# FPGA_board_controller_sheet.net
KiCad netlist of a schematic drawn in Altium Designer
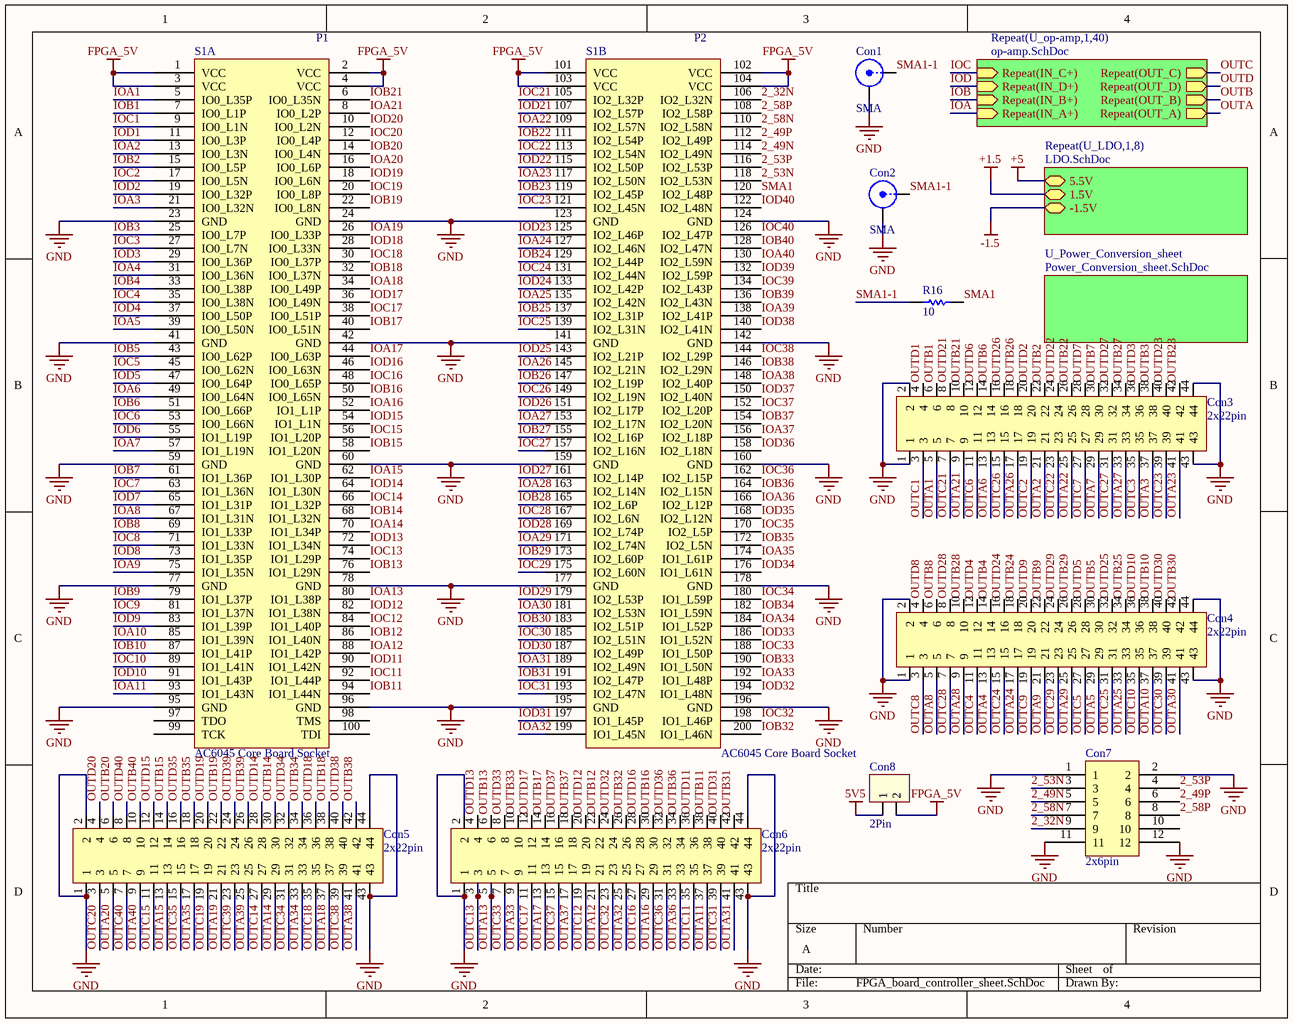
[diagram p0: FPGA_board_controller_sheet.SchDoc]

(export (version "E")
  (design (tool "Eeschema 10.0.6"))
  (components
    (comp (ref "Con1")
      (value "SMA")
      (footprint "SMA (3.5mm)")
      (libsource (lib "Schlib_FPGA_Controller") (part "SMA"))
    )
    (comp (ref "Con2")
      (value "SMA")
      (footprint "SMA (3.5mm)")
      (libsource (lib "Schlib_FPGA_Controller") (part "SMA"))
    )
    (comp (ref "Con3")
      (value "2x22pin")
      (footprint "2mm_2x22pin")
      (libsource (lib "Schlib_FPGA_Controller") (part "2x22pin"))
    )
    (comp (ref "Con4")
      (value "2x22pin")
      (footprint "2mm_2x22pin")
      (libsource (lib "Schlib_FPGA_Controller") (part "2x22pin"))
    )
    (comp (ref "Con5")
      (value "2x22pin")
      (footprint "2mm_2x22pin")
      (libsource (lib "Schlib_FPGA_Controller") (part "2x22pin"))
    )
    (comp (ref "Con6")
      (value "2x22pin")
      (footprint "2mm_2x22pin")
      (libsource (lib "Schlib_FPGA_Controller") (part "2x22pin"))
    )
    (comp (ref "Con7")
      (value "2x6pin")
      (footprint "2MM_2*6PIN")
      (libsource (lib "Schlib_FPGA_Controller") (part "2x6pin"))
    )
    (comp (ref "Con8")
      (value "2Pin")
      (footprint "XH2.54-2pin")
      (libsource (lib "Schlib_FPGA_Controller") (part "2Pin"))
    )
    (comp (ref "R16")
      (value "10")
      (footprint "R0603")
      (libsource (lib "Schlib_FPGA_Controller") (part "Resistor"))
    )
    (comp (ref "S1")
      (value "AC6045 Core Board Socket")
      (footprint "Core Board Socket")
      (libsource (lib "Schlib_FPGA_Controller") (part "AC6045 Core Board Socket"))
    )
  )
  (nets
    (net (code "4") (name "/2_32N") (class "Default")
      (node (ref "Con7") (pin "9") (pinfunction "9_9") (pintype "passive"))
      (node (ref "S1") (pin "106") (pinfunction "IO2_L32N_106") (pintype "passive"))
    )
    (net (code "5") (name "/2_49N") (class "Default")
      (node (ref "Con7") (pin "5") (pinfunction "5_5") (pintype "passive"))
      (node (ref "S1") (pin "114") (pinfunction "IO2_L49N_114") (pintype "passive"))
    )
    (net (code "6") (name "/2_49P") (class "Default")
      (node (ref "Con7") (pin "6") (pinfunction "6_6") (pintype "passive"))
      (node (ref "S1") (pin "112") (pinfunction "IO2_L49P_112") (pintype "passive"))
    )
    (net (code "7") (name "/2_53N") (class "Default")
      (node (ref "Con7") (pin "3") (pinfunction "3_3") (pintype "passive"))
      (node (ref "S1") (pin "118") (pinfunction "IO2_L53N_118") (pintype "passive"))
    )
    (net (code "8") (name "/2_53P") (class "Default")
      (node (ref "Con7") (pin "4") (pinfunction "4_4") (pintype "passive"))
      (node (ref "S1") (pin "116") (pinfunction "IO2_L53P_116") (pintype "passive"))
    )
    (net (code "9") (name "/2_58N") (class "Default")
      (node (ref "Con7") (pin "7") (pinfunction "7_7") (pintype "passive"))
      (node (ref "S1") (pin "110") (pinfunction "IO2_L58N_110") (pintype "passive"))
    )
    (net (code "10") (name "/2_58P") (class "Default")
      (node (ref "Con7") (pin "8") (pinfunction "8_8") (pintype "passive"))
      (node (ref "S1") (pin "108") (pinfunction "IO2_L58P_108") (pintype "passive"))
    )
    (net (code "12") (name "/IOA1") (class "Default")
      (node (ref "S1") (pin "5") (pinfunction "IO0_L35P_5") (pintype "passive"))
    )
    (net (code "13") (name "/IOA2") (class "Default")
      (node (ref "S1") (pin "13") (pinfunction "IO0_L3N_13") (pintype "passive"))
    )
    (net (code "14") (name "/IOA3") (class "Default")
      (node (ref "S1") (pin "21") (pinfunction "IO0_L32N_21") (pintype "passive"))
    )
    (net (code "15") (name "/IOA4") (class "Default")
      (node (ref "S1") (pin "31") (pinfunction "IO0_L36N_31") (pintype "passive"))
    )
    (net (code "16") (name "/IOA5") (class "Default")
      (node (ref "S1") (pin "39") (pinfunction "IO0_L50N_39") (pintype "passive"))
    )
    (net (code "17") (name "/IOA6") (class "Default")
      (node (ref "S1") (pin "49") (pinfunction "IO0_L64N_49") (pintype "passive"))
    )
    (net (code "18") (name "/IOA7") (class "Default")
      (node (ref "S1") (pin "57") (pinfunction "IO1_L19N_57") (pintype "passive"))
    )
    (net (code "19") (name "/IOA8") (class "Default")
      (node (ref "S1") (pin "67") (pinfunction "IO1_L31N_67") (pintype "passive"))
    )
    (net (code "20") (name "/IOA9") (class "Default")
      (node (ref "S1") (pin "75") (pinfunction "IO1_L35N_75") (pintype "passive"))
    )
    (net (code "21") (name "/IOA10") (class "Default")
      (node (ref "S1") (pin "85") (pinfunction "IO1_L39N_85") (pintype "passive"))
    )
    (net (code "22") (name "/IOA11") (class "Default")
      (node (ref "S1") (pin "93") (pinfunction "IO1_L43N_93") (pintype "passive"))
    )
    (net (code "23") (name "/IOA12") (class "Default")
      (node (ref "S1") (pin "88") (pinfunction "IO1_L42P_88") (pintype "passive"))
    )
    (net (code "24") (name "/IOA13") (class "Default")
      (node (ref "S1") (pin "80") (pinfunction "IO1_L38P_80") (pintype "passive"))
    )
    (net (code "25") (name "/IOA14") (class "Default")
      (node (ref "S1") (pin "70") (pinfunction "IO1_L34P_70") (pintype "passive"))
    )
    (net (code "26") (name "/IOA15") (class "Default")
      (node (ref "S1") (pin "62") (pinfunction "IO1_L30P_62") (pintype "passive"))
    )
    (net (code "27") (name "/IOA16") (class "Default")
      (node (ref "S1") (pin "52") (pinfunction "IO1_L1P_52") (pintype "passive"))
    )
    (net (code "28") (name "/IOA17") (class "Default")
      (node (ref "S1") (pin "44") (pinfunction "IO0_L63P_44") (pintype "passive"))
    )
    (net (code "29") (name "/IOA18") (class "Default")
      (node (ref "S1") (pin "34") (pinfunction "IO0_L49P_34") (pintype "passive"))
    )
    (net (code "30") (name "/IOA19") (class "Default")
      (node (ref "S1") (pin "26") (pinfunction "IO0_L33P_26") (pintype "passive"))
    )
    (net (code "31") (name "/IOA20") (class "Default")
      (node (ref "S1") (pin "16") (pinfunction "IO0_L6P_16") (pintype "passive"))
    )
    (net (code "32") (name "/IOA21") (class "Default")
      (node (ref "S1") (pin "8") (pinfunction "IO0_L2P_8") (pintype "passive"))
    )
    (net (code "33") (name "/IOA22") (class "Default")
      (node (ref "S1") (pin "109") (pinfunction "IO2_L57N_109") (pintype "passive"))
    )
    (net (code "34") (name "/IOA23") (class "Default")
      (node (ref "S1") (pin "117") (pinfunction "IO2_L50N_117") (pintype "passive"))
    )
    (net (code "35") (name "/IOA24") (class "Default")
      (node (ref "S1") (pin "127") (pinfunction "IO2_L46N_127") (pintype "passive"))
    )
    (net (code "36") (name "/IOA25") (class "Default")
      (node (ref "S1") (pin "135") (pinfunction "IO2_L42N_135") (pintype "passive"))
    )
    (net (code "37") (name "/IOA26") (class "Default")
      (node (ref "S1") (pin "145") (pinfunction "IO2_L21N_145") (pintype "passive"))
    )
    (net (code "38") (name "/IOA27") (class "Default")
      (node (ref "S1") (pin "153") (pinfunction "IO2_L17N_153") (pintype "passive"))
    )
    (net (code "39") (name "/IOA28") (class "Default")
      (node (ref "S1") (pin "163") (pinfunction "IO2_L14N_163") (pintype "passive"))
    )
    (net (code "40") (name "/IOA29") (class "Default")
      (node (ref "S1") (pin "171") (pinfunction "IO2_L74N_171") (pintype "passive"))
    )
    (net (code "41") (name "/IOA30") (class "Default")
      (node (ref "S1") (pin "181") (pinfunction "IO2_L53N_181") (pintype "passive"))
    )
    (net (code "42") (name "/IOA31") (class "Default")
      (node (ref "S1") (pin "189") (pinfunction "IO2_L49N_189") (pintype "passive"))
    )
    (net (code "43") (name "/IOA32") (class "Default")
      (node (ref "S1") (pin "199") (pinfunction "IO1_L45N_199") (pintype "passive"))
    )
    (net (code "44") (name "/IOA33") (class "Default")
      (node (ref "S1") (pin "192") (pinfunction "IO1_L48P_192") (pintype "passive"))
    )
    (net (code "45") (name "/IOA34") (class "Default")
      (node (ref "S1") (pin "184") (pinfunction "IO1_L52P_184") (pintype "passive"))
    )
    (net (code "46") (name "/IOA35") (class "Default")
      (node (ref "S1") (pin "174") (pinfunction "IO1_L61P_174") (pintype "passive"))
    )
    (net (code "47") (name "/IOA36") (class "Default")
      (node (ref "S1") (pin "166") (pinfunction "IO2_L12P_166") (pintype "passive"))
    )
    (net (code "48") (name "/IOA37") (class "Default")
      (node (ref "S1") (pin "156") (pinfunction "IO2_L18P_156") (pintype "passive"))
    )
    (net (code "49") (name "/IOA38") (class "Default")
      (node (ref "S1") (pin "148") (pinfunction "IO2_L40P_148") (pintype "passive"))
    )
    (net (code "50") (name "/IOA39") (class "Default")
      (node (ref "S1") (pin "138") (pinfunction "IO2_L41P_138") (pintype "passive"))
    )
    (net (code "51") (name "/IOA40") (class "Default")
      (node (ref "S1") (pin "130") (pinfunction "IO2_L59N_130") (pintype "passive"))
    )
    (net (code "53") (name "/IOB1") (class "Default")
      (node (ref "S1") (pin "7") (pinfunction "IO0_L1P_7") (pintype "passive"))
    )
    (net (code "54") (name "/IOB2") (class "Default")
      (node (ref "S1") (pin "15") (pinfunction "IO0_L5P_15") (pintype "passive"))
    )
    (net (code "55") (name "/IOB3") (class "Default")
      (node (ref "S1") (pin "25") (pinfunction "IO0_L7P_25") (pintype "passive"))
    )
    (net (code "56") (name "/IOB4") (class "Default")
      (node (ref "S1") (pin "33") (pinfunction "IO0_L38P_33") (pintype "passive"))
    )
    (net (code "57") (name "/IOB5") (class "Default")
      (node (ref "S1") (pin "43") (pinfunction "IO0_L62P_43") (pintype "passive"))
    )
    (net (code "58") (name "/IOB6") (class "Default")
      (node (ref "S1") (pin "51") (pinfunction "IO0_L66P_51") (pintype "passive"))
    )
    (net (code "59") (name "/IOB7") (class "Default")
      (node (ref "S1") (pin "61") (pinfunction "IO1_L36P_61") (pintype "passive"))
    )
    (net (code "60") (name "/IOB8") (class "Default")
      (node (ref "S1") (pin "69") (pinfunction "IO1_L33P_69") (pintype "passive"))
    )
    (net (code "61") (name "/IOB9") (class "Default")
      (node (ref "S1") (pin "79") (pinfunction "IO1_L37P_79") (pintype "passive"))
    )
    (net (code "62") (name "/IOB10") (class "Default")
      (node (ref "S1") (pin "87") (pinfunction "IO1_L41P_87") (pintype "passive"))
    )
    (net (code "63") (name "/IOB11") (class "Default")
      (node (ref "S1") (pin "94") (pinfunction "IO1_L44N_94") (pintype "passive"))
    )
    (net (code "64") (name "/IOB12") (class "Default")
      (node (ref "S1") (pin "86") (pinfunction "IO1_L40N_86") (pintype "passive"))
    )
    (net (code "65") (name "/IOB13") (class "Default")
      (node (ref "S1") (pin "76") (pinfunction "IO1_L29N_76") (pintype "passive"))
    )
    (net (code "66") (name "/IOB14") (class "Default")
      (node (ref "S1") (pin "68") (pinfunction "IO1_L32N_68") (pintype "passive"))
    )
    (net (code "67") (name "/IOB15") (class "Default")
      (node (ref "S1") (pin "58") (pinfunction "IO1_L20N_58") (pintype "passive"))
    )
    (net (code "68") (name "/IOB16") (class "Default")
      (node (ref "S1") (pin "50") (pinfunction "IO0_L65N_50") (pintype "passive"))
    )
    (net (code "69") (name "/IOB17") (class "Default")
      (node (ref "S1") (pin "40") (pinfunction "IO0_L51N_40") (pintype "passive"))
    )
    (net (code "70") (name "/IOB18") (class "Default")
      (node (ref "S1") (pin "32") (pinfunction "IO0_L37N_32") (pintype "passive"))
    )
    (net (code "71") (name "/IOB19") (class "Default")
      (node (ref "S1") (pin "22") (pinfunction "IO0_L8N_22") (pintype "passive"))
    )
    (net (code "72") (name "/IOB20") (class "Default")
      (node (ref "S1") (pin "14") (pinfunction "IO0_L4N_14") (pintype "passive"))
    )
    (net (code "73") (name "/IOB21") (class "Default")
      (node (ref "S1") (pin "6") (pinfunction "IO0_L35N_6") (pintype "passive"))
    )
    (net (code "74") (name "/IOB22") (class "Default")
      (node (ref "S1") (pin "111") (pinfunction "IO2_L54P_111") (pintype "passive"))
    )
    (net (code "75") (name "/IOB23") (class "Default")
      (node (ref "S1") (pin "119") (pinfunction "IO2_L45P_119") (pintype "passive"))
    )
    (net (code "76") (name "/IOB24") (class "Default")
      (node (ref "S1") (pin "129") (pinfunction "IO2_L44P_129") (pintype "passive"))
    )
    (net (code "77") (name "/IOB25") (class "Default")
      (node (ref "S1") (pin "137") (pinfunction "IO2_L31P_137") (pintype "passive"))
    )
    (net (code "78") (name "/IOB26") (class "Default")
      (node (ref "S1") (pin "147") (pinfunction "IO2_L19P_147") (pintype "passive"))
    )
    (net (code "79") (name "/IOB27") (class "Default")
      (node (ref "S1") (pin "155") (pinfunction "IO2_L16P_155") (pintype "passive"))
    )
    (net (code "80") (name "/IOB28") (class "Default")
      (node (ref "S1") (pin "165") (pinfunction "IO2_L6P_165") (pintype "passive"))
    )
    (net (code "81") (name "/IOB29") (class "Default")
      (node (ref "S1") (pin "173") (pinfunction "IO2_L60P_173") (pintype "passive"))
    )
    (net (code "82") (name "/IOB30") (class "Default")
      (node (ref "S1") (pin "183") (pinfunction "IO2_L51P_183") (pintype "passive"))
    )
    (net (code "83") (name "/IOB31") (class "Default")
      (node (ref "S1") (pin "191") (pinfunction "IO2_L47P_191") (pintype "passive"))
    )
    (net (code "84") (name "/IOB32") (class "Default")
      (node (ref "S1") (pin "200") (pinfunction "IO1_L46N_200") (pintype "passive"))
    )
    (net (code "85") (name "/IOB33") (class "Default")
      (node (ref "S1") (pin "190") (pinfunction "IO1_L50N_190") (pintype "passive"))
    )
    (net (code "86") (name "/IOB34") (class "Default")
      (node (ref "S1") (pin "182") (pinfunction "IO1_L59N_182") (pintype "passive"))
    )
    (net (code "87") (name "/IOB35") (class "Default")
      (node (ref "S1") (pin "172") (pinfunction "IO2_L5N_172") (pintype "passive"))
    )
    (net (code "88") (name "/IOB36") (class "Default")
      (node (ref "S1") (pin "164") (pinfunction "IO2_L15N_164") (pintype "passive"))
    )
    (net (code "89") (name "/IOB37") (class "Default")
      (node (ref "S1") (pin "154") (pinfunction "IO2_L20N_154") (pintype "passive"))
    )
    (net (code "90") (name "/IOB38") (class "Default")
      (node (ref "S1") (pin "146") (pinfunction "IO2_L29N_146") (pintype "passive"))
    )
    (net (code "91") (name "/IOB39") (class "Default")
      (node (ref "S1") (pin "136") (pinfunction "IO2_L43N_136") (pintype "passive"))
    )
    (net (code "92") (name "/IOB40") (class "Default")
      (node (ref "S1") (pin "128") (pinfunction "IO2_L47N_128") (pintype "passive"))
    )
    (net (code "94") (name "/IOC1") (class "Default")
      (node (ref "S1") (pin "9") (pinfunction "IO0_L1N_9") (pintype "passive"))
    )
    (net (code "95") (name "/IOC2") (class "Default")
      (node (ref "S1") (pin "17") (pinfunction "IO0_L5N_17") (pintype "passive"))
    )
    (net (code "96") (name "/IOC3") (class "Default")
      (node (ref "S1") (pin "27") (pinfunction "IO0_L7N_27") (pintype "passive"))
    )
    (net (code "97") (name "/IOC4") (class "Default")
      (node (ref "S1") (pin "35") (pinfunction "IO0_L38N_35") (pintype "passive"))
    )
    (net (code "98") (name "/IOC5") (class "Default")
      (node (ref "S1") (pin "45") (pinfunction "IO0_L62N_45") (pintype "passive"))
    )
    (net (code "99") (name "/IOC6") (class "Default")
      (node (ref "S1") (pin "53") (pinfunction "IO0_L66N_53") (pintype "passive"))
    )
    (net (code "100") (name "/IOC7") (class "Default")
      (node (ref "S1") (pin "63") (pinfunction "IO1_L36N_63") (pintype "passive"))
    )
    (net (code "101") (name "/IOC8") (class "Default")
      (node (ref "S1") (pin "71") (pinfunction "IO1_L33N_71") (pintype "passive"))
    )
    (net (code "102") (name "/IOC9") (class "Default")
      (node (ref "S1") (pin "81") (pinfunction "IO1_L37N_81") (pintype "passive"))
    )
    (net (code "103") (name "/IOC10") (class "Default")
      (node (ref "S1") (pin "89") (pinfunction "IO1_L41N_89") (pintype "passive"))
    )
    (net (code "104") (name "/IOC11") (class "Default")
      (node (ref "S1") (pin "92") (pinfunction "IO1_L44P_92") (pintype "passive"))
    )
    (net (code "105") (name "/IOC12") (class "Default")
      (node (ref "S1") (pin "84") (pinfunction "IO1_L40P_84") (pintype "passive"))
    )
    (net (code "106") (name "/IOC13") (class "Default")
      (node (ref "S1") (pin "74") (pinfunction "IO1_L29P_74") (pintype "passive"))
    )
    (net (code "107") (name "/IOC14") (class "Default")
      (node (ref "S1") (pin "66") (pinfunction "IO1_L32P_66") (pintype "passive"))
    )
    (net (code "108") (name "/IOC15") (class "Default")
      (node (ref "S1") (pin "56") (pinfunction "IO1_L20P_56") (pintype "passive"))
    )
    (net (code "109") (name "/IOC16") (class "Default")
      (node (ref "S1") (pin "48") (pinfunction "IO0_L65P_48") (pintype "passive"))
    )
    (net (code "110") (name "/IOC17") (class "Default")
      (node (ref "S1") (pin "38") (pinfunction "IO0_L51P_38") (pintype "passive"))
    )
    (net (code "111") (name "/IOC18") (class "Default")
      (node (ref "S1") (pin "30") (pinfunction "IO0_L37P_30") (pintype "passive"))
    )
    (net (code "112") (name "/IOC19") (class "Default")
      (node (ref "S1") (pin "20") (pinfunction "IO0_L8P_20") (pintype "passive"))
    )
    (net (code "113") (name "/IOC20") (class "Default")
      (node (ref "S1") (pin "12") (pinfunction "IO0_L4P_12") (pintype "passive"))
    )
    (net (code "114") (name "/IOC21") (class "Default")
      (node (ref "S1") (pin "105") (pinfunction "IO2_L32P_105") (pintype "passive"))
    )
    (net (code "115") (name "/IOC22") (class "Default")
      (node (ref "S1") (pin "113") (pinfunction "IO2_L54N_113") (pintype "passive"))
    )
    (net (code "116") (name "/IOC23") (class "Default")
      (node (ref "S1") (pin "121") (pinfunction "IO2_L45N_121") (pintype "passive"))
    )
    (net (code "117") (name "/IOC24") (class "Default")
      (node (ref "S1") (pin "131") (pinfunction "IO2_L44N_131") (pintype "passive"))
    )
    (net (code "118") (name "/IOC25") (class "Default")
      (node (ref "S1") (pin "139") (pinfunction "IO2_L31N_139") (pintype "passive"))
    )
    (net (code "119") (name "/IOC26") (class "Default")
      (node (ref "S1") (pin "149") (pinfunction "IO2_L19N_149") (pintype "passive"))
    )
    (net (code "120") (name "/IOC27") (class "Default")
      (node (ref "S1") (pin "157") (pinfunction "IO2_L16N_157") (pintype "passive"))
    )
    (net (code "121") (name "/IOC28") (class "Default")
      (node (ref "S1") (pin "167") (pinfunction "IO2_L6N_167") (pintype "passive"))
    )
    (net (code "122") (name "/IOC29") (class "Default")
      (node (ref "S1") (pin "175") (pinfunction "IO2_L60N_175") (pintype "passive"))
    )
    (net (code "123") (name "/IOC30") (class "Default")
      (node (ref "S1") (pin "185") (pinfunction "IO2_L51N_185") (pintype "passive"))
    )
    (net (code "124") (name "/IOC31") (class "Default")
      (node (ref "S1") (pin "193") (pinfunction "IO2_L47N_193") (pintype "passive"))
    )
    (net (code "125") (name "/IOC32") (class "Default")
      (node (ref "S1") (pin "198") (pinfunction "IO1_L46P_198") (pintype "passive"))
    )
    (net (code "126") (name "/IOC33") (class "Default")
      (node (ref "S1") (pin "188") (pinfunction "IO1_L50P_188") (pintype "passive"))
    )
    (net (code "127") (name "/IOC34") (class "Default")
      (node (ref "S1") (pin "180") (pinfunction "IO1_L59P_180") (pintype "passive"))
    )
    (net (code "128") (name "/IOC35") (class "Default")
      (node (ref "S1") (pin "170") (pinfunction "IO2_L5P_170") (pintype "passive"))
    )
    (net (code "129") (name "/IOC36") (class "Default")
      (node (ref "S1") (pin "162") (pinfunction "IO2_L15P_162") (pintype "passive"))
    )
    (net (code "130") (name "/IOC37") (class "Default")
      (node (ref "S1") (pin "152") (pinfunction "IO2_L20P_152") (pintype "passive"))
    )
    (net (code "131") (name "/IOC38") (class "Default")
      (node (ref "S1") (pin "144") (pinfunction "IOS_L29P_144") (pintype "passive"))
    )
    (net (code "132") (name "/IOC39") (class "Default")
      (node (ref "S1") (pin "134") (pinfunction "IO2_L43P_134") (pintype "passive"))
    )
    (net (code "133") (name "/IOC40") (class "Default")
      (node (ref "S1") (pin "126") (pinfunction "IO2_L47P_126") (pintype "passive"))
    )
    (net (code "135") (name "/IOD1") (class "Default")
      (node (ref "S1") (pin "11") (pinfunction "IO0_L3P_11") (pintype "passive"))
    )
    (net (code "136") (name "/IOD2") (class "Default")
      (node (ref "S1") (pin "19") (pinfunction "IO0_L32P_19") (pintype "passive"))
    )
    (net (code "137") (name "/IOD3") (class "Default")
      (node (ref "S1") (pin "29") (pinfunction "IO0_L36P_29") (pintype "passive"))
    )
    (net (code "138") (name "/IOD4") (class "Default")
      (node (ref "S1") (pin "37") (pinfunction "IO0_L50P_37") (pintype "passive"))
    )
    (net (code "139") (name "/IOD5") (class "Default")
      (node (ref "S1") (pin "47") (pinfunction "IO0_L64P_47") (pintype "passive"))
    )
    (net (code "140") (name "/IOD6") (class "Default")
      (node (ref "S1") (pin "55") (pinfunction "IO1_L19P_55") (pintype "passive"))
    )
    (net (code "141") (name "/IOD7") (class "Default")
      (node (ref "S1") (pin "65") (pinfunction "IO1_L31P_65") (pintype "passive"))
    )
    (net (code "142") (name "/IOD8") (class "Default")
      (node (ref "S1") (pin "73") (pinfunction "IO1_L35P_73") (pintype "passive"))
    )
    (net (code "143") (name "/IOD9") (class "Default")
      (node (ref "S1") (pin "83") (pinfunction "IO1_L39P_83") (pintype "passive"))
    )
    (net (code "144") (name "/IOD10") (class "Default")
      (node (ref "S1") (pin "91") (pinfunction "IO1_L43P_91") (pintype "passive"))
    )
    (net (code "145") (name "/IOD11") (class "Default")
      (node (ref "S1") (pin "90") (pinfunction "IO1_L42N_90") (pintype "passive"))
    )
    (net (code "146") (name "/IOD12") (class "Default")
      (node (ref "S1") (pin "82") (pinfunction "IO1_L38N_82") (pintype "passive"))
    )
    (net (code "147") (name "/IOD13") (class "Default")
      (node (ref "S1") (pin "72") (pinfunction "IO1_L34N_72") (pintype "passive"))
    )
    (net (code "148") (name "/IOD14") (class "Default")
      (node (ref "S1") (pin "64") (pinfunction "IO1_L30N_64") (pintype "passive"))
    )
    (net (code "149") (name "/IOD15") (class "Default")
      (node (ref "S1") (pin "54") (pinfunction "IO1_L1N_54") (pintype "passive"))
    )
    (net (code "150") (name "/IOD16") (class "Default")
      (node (ref "S1") (pin "46") (pinfunction "IO0_L63N_46") (pintype "passive"))
    )
    (net (code "151") (name "/IOD17") (class "Default")
      (node (ref "S1") (pin "36") (pinfunction "IO0_L49N_36") (pintype "passive"))
    )
    (net (code "152") (name "/IOD18") (class "Default")
      (node (ref "S1") (pin "28") (pinfunction "IO0_L33N_28") (pintype "passive"))
    )
    (net (code "153") (name "/IOD19") (class "Default")
      (node (ref "S1") (pin "18") (pinfunction "IO0_L6N_18") (pintype "passive"))
    )
    (net (code "154") (name "/IOD20") (class "Default")
      (node (ref "S1") (pin "10") (pinfunction "IO0_L2N_10") (pintype "passive"))
    )
    (net (code "155") (name "/IOD21") (class "Default")
      (node (ref "S1") (pin "107") (pinfunction "IO2_L57P_107") (pintype "passive"))
    )
    (net (code "156") (name "/IOD22") (class "Default")
      (node (ref "S1") (pin "115") (pinfunction "IO2_L50P_115") (pintype "passive"))
    )
    (net (code "157") (name "/IOD23") (class "Default")
      (node (ref "S1") (pin "125") (pinfunction "IO2_L46P_125") (pintype "passive"))
    )
    (net (code "158") (name "/IOD24") (class "Default")
      (node (ref "S1") (pin "133") (pinfunction "IO2_L42P_133") (pintype "passive"))
    )
    (net (code "159") (name "/IOD25") (class "Default")
      (node (ref "S1") (pin "143") (pinfunction "IO2_L21P_143") (pintype "passive"))
    )
    (net (code "160") (name "/IOD26") (class "Default")
      (node (ref "S1") (pin "151") (pinfunction "IO2_L17P_151") (pintype "passive"))
    )
    (net (code "161") (name "/IOD27") (class "Default")
      (node (ref "S1") (pin "161") (pinfunction "IO2_L14P_161") (pintype "passive"))
    )
    (net (code "162") (name "/IOD28") (class "Default")
      (node (ref "S1") (pin "169") (pinfunction "IO2_L74P_169") (pintype "passive"))
    )
    (net (code "163") (name "/IOD29") (class "Default")
      (node (ref "S1") (pin "179") (pinfunction "IO2_L53P_179") (pintype "passive"))
    )
    (net (code "164") (name "/IOD30") (class "Default")
      (node (ref "S1") (pin "187") (pinfunction "IO2_L49P_187") (pintype "passive"))
    )
    (net (code "165") (name "/IOD31") (class "Default")
      (node (ref "S1") (pin "197") (pinfunction "IO1_L45P_197") (pintype "passive"))
    )
    (net (code "166") (name "/IOD32") (class "Default")
      (node (ref "S1") (pin "194") (pinfunction "IO1_L48N_194") (pintype "passive"))
    )
    (net (code "167") (name "/IOD33") (class "Default")
      (node (ref "S1") (pin "186") (pinfunction "IO1_L52N_186") (pintype "passive"))
    )
    (net (code "168") (name "/IOD34") (class "Default")
      (node (ref "S1") (pin "176") (pinfunction "IO1_L61N_176") (pintype "passive"))
    )
    (net (code "169") (name "/IOD35") (class "Default")
      (node (ref "S1") (pin "168") (pinfunction "IO2_L12N_168") (pintype "passive"))
    )
    (net (code "170") (name "/IOD36") (class "Default")
      (node (ref "S1") (pin "158") (pinfunction "IO2_L18N_158") (pintype "passive"))
    )
    (net (code "171") (name "/IOD37") (class "Default")
      (node (ref "S1") (pin "150") (pinfunction "IO2_L40N_150") (pintype "passive"))
    )
    (net (code "172") (name "/IOD38") (class "Default")
      (node (ref "S1") (pin "140") (pinfunction "IO2_L41N_140") (pintype "passive"))
    )
    (net (code "173") (name "/IOD39") (class "Default")
      (node (ref "S1") (pin "132") (pinfunction "IO2_L59P_132") (pintype "passive"))
    )
    (net (code "174") (name "/IOD40") (class "Default")
      (node (ref "S1") (pin "122") (pinfunction "IO2_L48N_122") (pintype "passive"))
    )
    (net (code "176") (name "/OUTA1") (class "Default")
      (node (ref "Con3") (pin "5") (pinfunction "5_5") (pintype "passive"))
    )
    (net (code "177") (name "/OUTA2") (class "Default")
      (node (ref "Con3") (pin "21") (pinfunction "21_21") (pintype "passive"))
    )
    (net (code "178") (name "/OUTA3") (class "Default")
      (node (ref "Con3") (pin "37") (pinfunction "37_37") (pintype "passive"))
    )
    (net (code "179") (name "/OUTA4") (class "Default")
      (node (ref "Con4") (pin "13") (pinfunction "13_13") (pintype "passive"))
    )
    (net (code "180") (name "/OUTA5") (class "Default")
      (node (ref "Con4") (pin "29") (pinfunction "29_29") (pintype "passive"))
    )
    (net (code "181") (name "/OUTA6") (class "Default")
      (node (ref "Con3") (pin "13") (pinfunction "13_13") (pintype "passive"))
    )
    (net (code "182") (name "/OUTA7") (class "Default")
      (node (ref "Con3") (pin "29") (pinfunction "29_29") (pintype "passive"))
    )
    (net (code "183") (name "/OUTA8") (class "Default")
      (node (ref "Con4") (pin "5") (pinfunction "5_5") (pintype "passive"))
    )
    (net (code "184") (name "/OUTA9") (class "Default")
      (node (ref "Con4") (pin "21") (pinfunction "21_21") (pintype "passive"))
    )
    (net (code "185") (name "/OUTA10") (class "Default")
      (node (ref "Con4") (pin "37") (pinfunction "37_37") (pintype "passive"))
    )
    (net (code "186") (name "/OUTA11") (class "Default")
      (node (ref "Con6") (pin "37") (pinfunction "37_37") (pintype "passive"))
    )
    (net (code "187") (name "/OUTA12") (class "Default")
      (node (ref "Con6") (pin "21") (pinfunction "21_21") (pintype "passive"))
    )
    (net (code "188") (name "/OUTA13") (class "Default")
      (node (ref "Con6") (pin "5") (pinfunction "5_5") (pintype "passive"))
    )
    (net (code "189") (name "/OUTA14") (class "Default")
      (node (ref "Con5") (pin "29") (pinfunction "29_29") (pintype "passive"))
    )
    (net (code "190") (name "/OUTA15") (class "Default")
      (node (ref "Con5") (pin "13") (pinfunction "13_13") (pintype "passive"))
    )
    (net (code "191") (name "/OUTA16") (class "Default")
      (node (ref "Con6") (pin "29") (pinfunction "29_29") (pintype "passive"))
    )
    (net (code "192") (name "/OUTA17") (class "Default")
      (node (ref "Con6") (pin "13") (pinfunction "13_13") (pintype "passive"))
    )
    (net (code "193") (name "/OUTA18") (class "Default")
      (node (ref "Con5") (pin "37") (pinfunction "37_37") (pintype "passive"))
    )
    (net (code "194") (name "/OUTA19") (class "Default")
      (node (ref "Con5") (pin "21") (pinfunction "21_21") (pintype "passive"))
    )
    (net (code "195") (name "/OUTA20") (class "Default")
      (node (ref "Con5") (pin "5") (pinfunction "5_5") (pintype "passive"))
    )
    (net (code "196") (name "/OUTA21") (class "Default")
      (node (ref "Con3") (pin "9") (pinfunction "9_9") (pintype "passive"))
    )
    (net (code "197") (name "/OUTA22") (class "Default")
      (node (ref "Con3") (pin "25") (pinfunction "25_25") (pintype "passive"))
    )
    (net (code "198") (name "/OUTA23") (class "Default")
      (node (ref "Con3") (pin "41") (pinfunction "41_41") (pintype "passive"))
    )
    (net (code "199") (name "/OUTA24") (class "Default")
      (node (ref "Con4") (pin "17") (pinfunction "17_17") (pintype "passive"))
    )
    (net (code "200") (name "/OUTA25") (class "Default")
      (node (ref "Con4") (pin "33") (pinfunction "33_33") (pintype "passive"))
    )
    (net (code "201") (name "/OUTA26") (class "Default")
      (node (ref "Con3") (pin "17") (pinfunction "17_17") (pintype "passive"))
    )
    (net (code "202") (name "/OUTA27") (class "Default")
      (node (ref "Con3") (pin "33") (pinfunction "33_33") (pintype "passive"))
    )
    (net (code "203") (name "/OUTA28") (class "Default")
      (node (ref "Con4") (pin "9") (pinfunction "9_9") (pintype "passive"))
    )
    (net (code "204") (name "/OUTA29") (class "Default")
      (node (ref "Con4") (pin "25") (pinfunction "25_25") (pintype "passive"))
    )
    (net (code "205") (name "/OUTA30") (class "Default")
      (node (ref "Con4") (pin "41") (pinfunction "41_41") (pintype "passive"))
    )
    (net (code "206") (name "/OUTA31") (class "Default")
      (node (ref "Con6") (pin "41") (pinfunction "41_41") (pintype "passive"))
    )
    (net (code "207") (name "/OUTA32") (class "Default")
      (node (ref "Con6") (pin "25") (pinfunction "25_25") (pintype "passive"))
    )
    (net (code "208") (name "/OUTA33") (class "Default")
      (node (ref "Con6") (pin "9") (pinfunction "9_9") (pintype "passive"))
    )
    (net (code "209") (name "/OUTA34") (class "Default")
      (node (ref "Con5") (pin "33") (pinfunction "33_33") (pintype "passive"))
    )
    (net (code "210") (name "/OUTA35") (class "Default")
      (node (ref "Con5") (pin "17") (pinfunction "17_17") (pintype "passive"))
    )
    (net (code "211") (name "/OUTA36") (class "Default")
      (node (ref "Con6") (pin "33") (pinfunction "33_33") (pintype "passive"))
    )
    (net (code "212") (name "/OUTA37") (class "Default")
      (node (ref "Con6") (pin "17") (pinfunction "17_17") (pintype "passive"))
    )
    (net (code "213") (name "/OUTA38") (class "Default")
      (node (ref "Con5") (pin "41") (pinfunction "41_41") (pintype "passive"))
    )
    (net (code "214") (name "/OUTA39") (class "Default")
      (node (ref "Con5") (pin "25") (pinfunction "25_25") (pintype "passive"))
    )
    (net (code "215") (name "/OUTA40") (class "Default")
      (node (ref "Con5") (pin "9") (pinfunction "9_9") (pintype "passive"))
    )
    (net (code "217") (name "/OUTB1") (class "Default")
      (node (ref "Con3") (pin "6") (pinfunction "6_6") (pintype "passive"))
    )
    (net (code "218") (name "/OUTB2") (class "Default")
      (node (ref "Con3") (pin "22") (pinfunction "22_22") (pintype "passive"))
    )
    (net (code "219") (name "/OUTB3") (class "Default")
      (node (ref "Con3") (pin "38") (pinfunction "38_38") (pintype "passive"))
    )
    (net (code "220") (name "/OUTB4") (class "Default")
      (node (ref "Con4") (pin "14") (pinfunction "14_14") (pintype "passive"))
    )
    (net (code "221") (name "/OUTB5") (class "Default")
      (node (ref "Con4") (pin "30") (pinfunction "30_30") (pintype "passive"))
    )
    (net (code "222") (name "/OUTB6") (class "Default")
      (node (ref "Con3") (pin "14") (pinfunction "14_14") (pintype "passive"))
    )
    (net (code "223") (name "/OUTB7") (class "Default")
      (node (ref "Con3") (pin "30") (pinfunction "30_30") (pintype "passive"))
    )
    (net (code "224") (name "/OUTB8") (class "Default")
      (node (ref "Con4") (pin "6") (pinfunction "6_6") (pintype "passive"))
    )
    (net (code "225") (name "/OUTB9") (class "Default")
      (node (ref "Con4") (pin "22") (pinfunction "22_22") (pintype "passive"))
    )
    (net (code "226") (name "/OUTB10") (class "Default")
      (node (ref "Con4") (pin "38") (pinfunction "38_38") (pintype "passive"))
    )
    (net (code "227") (name "/OUTB11") (class "Default")
      (node (ref "Con6") (pin "38") (pinfunction "38_38") (pintype "passive"))
    )
    (net (code "228") (name "/OUTB12") (class "Default")
      (node (ref "Con6") (pin "22") (pinfunction "22_22") (pintype "passive"))
    )
    (net (code "229") (name "/OUTB13") (class "Default")
      (node (ref "Con6") (pin "6") (pinfunction "6_6") (pintype "passive"))
    )
    (net (code "230") (name "/OUTB14") (class "Default")
      (node (ref "Con5") (pin "30") (pinfunction "30_30") (pintype "passive"))
    )
    (net (code "231") (name "/OUTB15") (class "Default")
      (node (ref "Con5") (pin "14") (pinfunction "14_14") (pintype "passive"))
    )
    (net (code "232") (name "/OUTB16") (class "Default")
      (node (ref "Con6") (pin "30") (pinfunction "30_30") (pintype "passive"))
    )
    (net (code "233") (name "/OUTB17") (class "Default")
      (node (ref "Con6") (pin "14") (pinfunction "14_14") (pintype "passive"))
    )
    (net (code "234") (name "/OUTB18") (class "Default")
      (node (ref "Con5") (pin "38") (pinfunction "38_38") (pintype "passive"))
    )
    (net (code "235") (name "/OUTB19") (class "Default")
      (node (ref "Con5") (pin "22") (pinfunction "22_22") (pintype "passive"))
    )
    (net (code "236") (name "/OUTB20") (class "Default")
      (node (ref "Con5") (pin "6") (pinfunction "6_6") (pintype "passive"))
    )
    (net (code "237") (name "/OUTB21") (class "Default")
      (node (ref "Con3") (pin "10") (pinfunction "10_10") (pintype "passive"))
    )
    (net (code "238") (name "/OUTB22") (class "Default")
      (node (ref "Con3") (pin "26") (pinfunction "26_26") (pintype "passive"))
    )
    (net (code "239") (name "/OUTB23") (class "Default")
      (node (ref "Con3") (pin "42") (pinfunction "42_42") (pintype "passive"))
    )
    (net (code "240") (name "/OUTB24") (class "Default")
      (node (ref "Con4") (pin "18") (pinfunction "18_18") (pintype "passive"))
    )
    (net (code "241") (name "/OUTB25") (class "Default")
      (node (ref "Con4") (pin "34") (pinfunction "34_34") (pintype "passive"))
    )
    (net (code "242") (name "/OUTB26") (class "Default")
      (node (ref "Con3") (pin "18") (pinfunction "18_18") (pintype "passive"))
    )
    (net (code "243") (name "/OUTB27") (class "Default")
      (node (ref "Con3") (pin "34") (pinfunction "34_34") (pintype "passive"))
    )
    (net (code "244") (name "/OUTB28") (class "Default")
      (node (ref "Con4") (pin "10") (pinfunction "10_10") (pintype "passive"))
    )
    (net (code "245") (name "/OUTB29") (class "Default")
      (node (ref "Con4") (pin "26") (pinfunction "26_26") (pintype "passive"))
    )
    (net (code "246") (name "/OUTB30") (class "Default")
      (node (ref "Con4") (pin "42") (pinfunction "42_42") (pintype "passive"))
    )
    (net (code "247") (name "/OUTB31") (class "Default")
      (node (ref "Con6") (pin "42") (pinfunction "42_42") (pintype "passive"))
    )
    (net (code "248") (name "/OUTB32") (class "Default")
      (node (ref "Con6") (pin "26") (pinfunction "26_26") (pintype "passive"))
    )
    (net (code "249") (name "/OUTB33") (class "Default")
      (node (ref "Con6") (pin "10") (pinfunction "10_10") (pintype "passive"))
    )
    (net (code "250") (name "/OUTB34") (class "Default")
      (node (ref "Con5") (pin "34") (pinfunction "34_34") (pintype "passive"))
    )
    (net (code "251") (name "/OUTB35") (class "Default")
      (node (ref "Con5") (pin "18") (pinfunction "18_18") (pintype "passive"))
    )
    (net (code "252") (name "/OUTB36") (class "Default")
      (node (ref "Con6") (pin "34") (pinfunction "34_34") (pintype "passive"))
    )
    (net (code "253") (name "/OUTB37") (class "Default")
      (node (ref "Con6") (pin "18") (pinfunction "18_18") (pintype "passive"))
    )
    (net (code "254") (name "/OUTB38") (class "Default")
      (node (ref "Con5") (pin "42") (pinfunction "42_42") (pintype "passive"))
    )
    (net (code "255") (name "/OUTB39") (class "Default")
      (node (ref "Con5") (pin "26") (pinfunction "26_26") (pintype "passive"))
    )
    (net (code "256") (name "/OUTB40") (class "Default")
      (node (ref "Con5") (pin "10") (pinfunction "10_10") (pintype "passive"))
    )
    (net (code "258") (name "/OUTC1") (class "Default")
      (node (ref "Con3") (pin "3") (pinfunction "3_3") (pintype "passive"))
    )
    (net (code "259") (name "/OUTC2") (class "Default")
      (node (ref "Con3") (pin "19") (pinfunction "19_19") (pintype "passive"))
    )
    (net (code "260") (name "/OUTC3") (class "Default")
      (node (ref "Con3") (pin "35") (pinfunction "35_35") (pintype "passive"))
    )
    (net (code "261") (name "/OUTC4") (class "Default")
      (node (ref "Con4") (pin "11") (pinfunction "11_11") (pintype "passive"))
    )
    (net (code "262") (name "/OUTC5") (class "Default")
      (node (ref "Con4") (pin "27") (pinfunction "27_27") (pintype "passive"))
    )
    (net (code "263") (name "/OUTC6") (class "Default")
      (node (ref "Con3") (pin "11") (pinfunction "11_11") (pintype "passive"))
    )
    (net (code "264") (name "/OUTC7") (class "Default")
      (node (ref "Con3") (pin "27") (pinfunction "27_27") (pintype "passive"))
    )
    (net (code "265") (name "/OUTC8") (class "Default")
      (node (ref "Con4") (pin "3") (pinfunction "3_3") (pintype "passive"))
    )
    (net (code "266") (name "/OUTC9") (class "Default")
      (node (ref "Con4") (pin "19") (pinfunction "19_19") (pintype "passive"))
    )
    (net (code "267") (name "/OUTC10") (class "Default")
      (node (ref "Con4") (pin "35") (pinfunction "35_35") (pintype "passive"))
    )
    (net (code "268") (name "/OUTC11") (class "Default")
      (node (ref "Con6") (pin "35") (pinfunction "35_35") (pintype "passive"))
    )
    (net (code "269") (name "/OUTC12") (class "Default")
      (node (ref "Con6") (pin "19") (pinfunction "19_19") (pintype "passive"))
    )
    (net (code "270") (name "/OUTC13") (class "Default")
      (node (ref "Con6") (pin "3") (pinfunction "3_3") (pintype "passive"))
    )
    (net (code "271") (name "/OUTC14") (class "Default")
      (node (ref "Con5") (pin "27") (pinfunction "27_27") (pintype "passive"))
    )
    (net (code "272") (name "/OUTC15") (class "Default")
      (node (ref "Con5") (pin "11") (pinfunction "11_11") (pintype "passive"))
    )
    (net (code "273") (name "/OUTC16") (class "Default")
      (node (ref "Con6") (pin "27") (pinfunction "27_27") (pintype "passive"))
    )
    (net (code "274") (name "/OUTC17") (class "Default")
      (node (ref "Con6") (pin "11") (pinfunction "11_11") (pintype "passive"))
    )
    (net (code "275") (name "/OUTC18") (class "Default")
      (node (ref "Con5") (pin "35") (pinfunction "35_35") (pintype "passive"))
    )
    (net (code "276") (name "/OUTC19") (class "Default")
      (node (ref "Con5") (pin "19") (pinfunction "19_19") (pintype "passive"))
    )
    (net (code "277") (name "/OUTC20") (class "Default")
      (node (ref "Con5") (pin "3") (pinfunction "3_3") (pintype "passive"))
    )
    (net (code "278") (name "/OUTC21") (class "Default")
      (node (ref "Con3") (pin "7") (pinfunction "7_7") (pintype "passive"))
    )
    (net (code "279") (name "/OUTC22") (class "Default")
      (node (ref "Con3") (pin "23") (pinfunction "23_23") (pintype "passive"))
    )
    (net (code "280") (name "/OUTC23") (class "Default")
      (node (ref "Con3") (pin "39") (pinfunction "39_39") (pintype "passive"))
    )
    (net (code "281") (name "/OUTC24") (class "Default")
      (node (ref "Con4") (pin "15") (pinfunction "15_15") (pintype "passive"))
    )
    (net (code "282") (name "/OUTC25") (class "Default")
      (node (ref "Con4") (pin "31") (pinfunction "31_31") (pintype "passive"))
    )
    (net (code "283") (name "/OUTC26") (class "Default")
      (node (ref "Con3") (pin "15") (pinfunction "15_15") (pintype "passive"))
    )
    (net (code "284") (name "/OUTC27") (class "Default")
      (node (ref "Con3") (pin "31") (pinfunction "31_31") (pintype "passive"))
    )
    (net (code "285") (name "/OUTC28") (class "Default")
      (node (ref "Con4") (pin "7") (pinfunction "7_7") (pintype "passive"))
    )
    (net (code "286") (name "/OUTC29") (class "Default")
      (node (ref "Con4") (pin "23") (pinfunction "23_23") (pintype "passive"))
    )
    (net (code "287") (name "/OUTC30") (class "Default")
      (node (ref "Con4") (pin "39") (pinfunction "39_39") (pintype "passive"))
    )
    (net (code "288") (name "/OUTC31") (class "Default")
      (node (ref "Con6") (pin "39") (pinfunction "39_39") (pintype "passive"))
    )
    (net (code "289") (name "/OUTC32") (class "Default")
      (node (ref "Con6") (pin "23") (pinfunction "23_23") (pintype "passive"))
    )
    (net (code "290") (name "/OUTC33") (class "Default")
      (node (ref "Con6") (pin "7") (pinfunction "7_7") (pintype "passive"))
    )
    (net (code "291") (name "/OUTC34") (class "Default")
      (node (ref "Con5") (pin "31") (pinfunction "31_31") (pintype "passive"))
    )
    (net (code "292") (name "/OUTC35") (class "Default")
      (node (ref "Con5") (pin "15") (pinfunction "15_15") (pintype "passive"))
    )
    (net (code "293") (name "/OUTC36") (class "Default")
      (node (ref "Con6") (pin "31") (pinfunction "31_31") (pintype "passive"))
    )
    (net (code "294") (name "/OUTC37") (class "Default")
      (node (ref "Con6") (pin "15") (pinfunction "15_15") (pintype "passive"))
    )
    (net (code "295") (name "/OUTC38") (class "Default")
      (node (ref "Con5") (pin "39") (pinfunction "39_39") (pintype "passive"))
    )
    (net (code "296") (name "/OUTC39") (class "Default")
      (node (ref "Con5") (pin "23") (pinfunction "23_23") (pintype "passive"))
    )
    (net (code "297") (name "/OUTC40") (class "Default")
      (node (ref "Con5") (pin "7") (pinfunction "7_7") (pintype "passive"))
    )
    (net (code "299") (name "/OUTD1") (class "Default")
      (node (ref "Con3") (pin "4") (pinfunction "4_4") (pintype "passive"))
    )
    (net (code "300") (name "/OUTD2") (class "Default")
      (node (ref "Con3") (pin "20") (pinfunction "20_20") (pintype "passive"))
    )
    (net (code "301") (name "/OUTD3") (class "Default")
      (node (ref "Con3") (pin "36") (pinfunction "36_36") (pintype "passive"))
    )
    (net (code "302") (name "/OUTD4") (class "Default")
      (node (ref "Con4") (pin "12") (pinfunction "12_12") (pintype "passive"))
    )
    (net (code "303") (name "/OUTD5") (class "Default")
      (node (ref "Con4") (pin "28") (pinfunction "28_28") (pintype "passive"))
    )
    (net (code "304") (name "/OUTD6") (class "Default")
      (node (ref "Con3") (pin "12") (pinfunction "12_12") (pintype "passive"))
    )
    (net (code "305") (name "/OUTD7") (class "Default")
      (node (ref "Con3") (pin "28") (pinfunction "28_28") (pintype "passive"))
    )
    (net (code "306") (name "/OUTD8") (class "Default")
      (node (ref "Con4") (pin "4") (pinfunction "4_4") (pintype "passive"))
    )
    (net (code "307") (name "/OUTD9") (class "Default")
      (node (ref "Con4") (pin "20") (pinfunction "20_20") (pintype "passive"))
    )
    (net (code "308") (name "/OUTD10") (class "Default")
      (node (ref "Con4") (pin "36") (pinfunction "36_36") (pintype "passive"))
    )
    (net (code "309") (name "/OUTD11") (class "Default")
      (node (ref "Con6") (pin "36") (pinfunction "36_36") (pintype "passive"))
    )
    (net (code "310") (name "/OUTD12") (class "Default")
      (node (ref "Con6") (pin "20") (pinfunction "20_20") (pintype "passive"))
    )
    (net (code "311") (name "/OUTD13") (class "Default")
      (node (ref "Con6") (pin "4") (pinfunction "4_4") (pintype "passive"))
    )
    (net (code "312") (name "/OUTD14") (class "Default")
      (node (ref "Con5") (pin "28") (pinfunction "28_28") (pintype "passive"))
    )
    (net (code "313") (name "/OUTD15") (class "Default")
      (node (ref "Con5") (pin "12") (pinfunction "12_12") (pintype "passive"))
    )
    (net (code "314") (name "/OUTD16") (class "Default")
      (node (ref "Con6") (pin "28") (pinfunction "28_28") (pintype "passive"))
    )
    (net (code "315") (name "/OUTD17") (class "Default")
      (node (ref "Con6") (pin "12") (pinfunction "12_12") (pintype "passive"))
    )
    (net (code "316") (name "/OUTD18") (class "Default")
      (node (ref "Con5") (pin "36") (pinfunction "36_36") (pintype "passive"))
    )
    (net (code "317") (name "/OUTD19") (class "Default")
      (node (ref "Con5") (pin "20") (pinfunction "20_20") (pintype "passive"))
    )
    (net (code "318") (name "/OUTD20") (class "Default")
      (node (ref "Con5") (pin "4") (pinfunction "4_4") (pintype "passive"))
    )
    (net (code "319") (name "/OUTD21") (class "Default")
      (node (ref "Con3") (pin "8") (pinfunction "8_8") (pintype "passive"))
    )
    (net (code "320") (name "/OUTD22") (class "Default")
      (node (ref "Con3") (pin "24") (pinfunction "24_24") (pintype "passive"))
    )
    (net (code "321") (name "/OUTD23") (class "Default")
      (node (ref "Con3") (pin "40") (pinfunction "40_40") (pintype "passive"))
    )
    (net (code "322") (name "/OUTD24") (class "Default")
      (node (ref "Con4") (pin "16") (pinfunction "16_16") (pintype "passive"))
    )
    (net (code "323") (name "/OUTD25") (class "Default")
      (node (ref "Con4") (pin "32") (pinfunction "32_32") (pintype "passive"))
    )
    (net (code "324") (name "/OUTD26") (class "Default")
      (node (ref "Con3") (pin "16") (pinfunction "16_16") (pintype "passive"))
    )
    (net (code "325") (name "/OUTD27") (class "Default")
      (node (ref "Con3") (pin "32") (pinfunction "32_32") (pintype "passive"))
    )
    (net (code "326") (name "/OUTD28") (class "Default")
      (node (ref "Con4") (pin "8") (pinfunction "8_8") (pintype "passive"))
    )
    (net (code "327") (name "/OUTD29") (class "Default")
      (node (ref "Con4") (pin "24") (pinfunction "24_24") (pintype "passive"))
    )
    (net (code "328") (name "/OUTD30") (class "Default")
      (node (ref "Con4") (pin "40") (pinfunction "40_40") (pintype "passive"))
    )
    (net (code "329") (name "/OUTD31") (class "Default")
      (node (ref "Con6") (pin "40") (pinfunction "40_40") (pintype "passive"))
    )
    (net (code "330") (name "/OUTD32") (class "Default")
      (node (ref "Con6") (pin "24") (pinfunction "24_24") (pintype "passive"))
    )
    (net (code "331") (name "/OUTD33") (class "Default")
      (node (ref "Con6") (pin "8") (pinfunction "8_8") (pintype "passive"))
    )
    (net (code "332") (name "/OUTD34") (class "Default")
      (node (ref "Con5") (pin "32") (pinfunction "32_32") (pintype "passive"))
    )
    (net (code "333") (name "/OUTD35") (class "Default")
      (node (ref "Con5") (pin "16") (pinfunction "16_16") (pintype "passive"))
    )
    (net (code "334") (name "/OUTD36") (class "Default")
      (node (ref "Con6") (pin "32") (pinfunction "32_32") (pintype "passive"))
    )
    (net (code "335") (name "/OUTD37") (class "Default")
      (node (ref "Con6") (pin "16") (pinfunction "16_16") (pintype "passive"))
    )
    (net (code "336") (name "/OUTD38") (class "Default")
      (node (ref "Con5") (pin "40") (pinfunction "40_40") (pintype "passive"))
    )
    (net (code "337") (name "/OUTD39") (class "Default")
      (node (ref "Con5") (pin "24") (pinfunction "24_24") (pintype "passive"))
    )
    (net (code "338") (name "/OUTD40") (class "Default")
      (node (ref "Con5") (pin "8") (pinfunction "8_8") (pintype "passive"))
    )
    (net (code "339") (name "/SMA1") (class "Default")
      (node (ref "R16") (pin "2") (pinfunction "2_2") (pintype "passive"))
      (node (ref "S1") (pin "120") (pinfunction "IO2_L48P_120") (pintype "passive"))
    )
    (net (code "340") (name "/SMA1-1") (class "Default")
      (node (ref "Con1") (pin "1") (pinfunction "X_1") (pintype "passive"))
      (node (ref "Con2") (pin "1") (pinfunction "X_1") (pintype "passive"))
      (node (ref "R16") (pin "1") (pinfunction "1_1") (pintype "passive"))
    )
    (net (code "341") (name "5V5") (class "Default")
      (node (ref "Con8") (pin "1") (pinfunction "1_1") (pintype "passive"))
    )
    (net (code "342") (name "FPGA_5V") (class "Default")
      (node (ref "Con8") (pin "2") (pinfunction "2_2") (pintype "passive"))
      (node (ref "S1") (pin "1") (pinfunction "VCC_1") (pintype "passive"))
      (node (ref "S1") (pin "101") (pinfunction "VCC_101") (pintype "passive"))
      (node (ref "S1") (pin "102") (pinfunction "VCC_102") (pintype "passive"))
      (node (ref "S1") (pin "103") (pinfunction "VCC_103") (pintype "passive"))
      (node (ref "S1") (pin "104") (pinfunction "VCC_104") (pintype "passive"))
      (node (ref "S1") (pin "2") (pinfunction "VCC_2") (pintype "passive"))
      (node (ref "S1") (pin "3") (pinfunction "VCC_3") (pintype "passive"))
      (node (ref "S1") (pin "4") (pinfunction "VCC_4") (pintype "passive"))
    )
    (net (code "343") (name "GND") (class "Default")
      (node (ref "Con1") (pin "2") (pinfunction "Y_2") (pintype "passive"))
      (node (ref "Con2") (pin "2") (pinfunction "Y_2") (pintype "passive"))
      (node (ref "Con3") (pin "1") (pinfunction "1_1") (pintype "passive"))
      (node (ref "Con3") (pin "2") (pinfunction "2_2") (pintype "passive"))
      (node (ref "Con3") (pin "43") (pinfunction "43_43") (pintype "passive"))
      (node (ref "Con3") (pin "44") (pinfunction "44_44") (pintype "passive"))
      (node (ref "Con4") (pin "1") (pinfunction "1_1") (pintype "passive"))
      (node (ref "Con4") (pin "2") (pinfunction "2_2") (pintype "passive"))
      (node (ref "Con4") (pin "43") (pinfunction "43_43") (pintype "passive"))
      (node (ref "Con4") (pin "44") (pinfunction "44_44") (pintype "passive"))
      (node (ref "Con5") (pin "1") (pinfunction "1_1") (pintype "passive"))
      (node (ref "Con5") (pin "2") (pinfunction "2_2") (pintype "passive"))
      (node (ref "Con5") (pin "43") (pinfunction "43_43") (pintype "passive"))
      (node (ref "Con5") (pin "44") (pinfunction "44_44") (pintype "passive"))
      (node (ref "Con6") (pin "1") (pinfunction "1_1") (pintype "passive"))
      (node (ref "Con6") (pin "2") (pinfunction "2_2") (pintype "passive"))
      (node (ref "Con6") (pin "43") (pinfunction "43_43") (pintype "passive"))
      (node (ref "Con6") (pin "44") (pinfunction "44_44") (pintype "passive"))
      (node (ref "Con7") (pin "1") (pinfunction "1_1") (pintype "passive"))
      (node (ref "Con7") (pin "11") (pinfunction "11_11") (pintype "passive"))
      (node (ref "Con7") (pin "12") (pinfunction "12_12") (pintype "passive"))
      (node (ref "Con7") (pin "2") (pinfunction "2_2") (pintype "passive"))
      (node (ref "S1") (pin "123") (pinfunction "GND_123") (pintype "passive"))
      (node (ref "S1") (pin "124") (pinfunction "GND_124") (pintype "passive"))
      (node (ref "S1") (pin "141") (pinfunction "GND_141") (pintype "passive"))
      (node (ref "S1") (pin "142") (pinfunction "GND_142") (pintype "passive"))
      (node (ref "S1") (pin "159") (pinfunction "GND_159") (pintype "passive"))
      (node (ref "S1") (pin "160") (pinfunction "GND_160") (pintype "passive"))
      (node (ref "S1") (pin "177") (pinfunction "GND_177") (pintype "passive"))
      (node (ref "S1") (pin "178") (pinfunction "GND_178") (pintype "passive"))
      (node (ref "S1") (pin "195") (pinfunction "GND_195") (pintype "passive"))
      (node (ref "S1") (pin "196") (pinfunction "GND_196") (pintype "passive"))
      (node (ref "S1") (pin "23") (pinfunction "GND_23") (pintype "passive"))
      (node (ref "S1") (pin "24") (pinfunction "GND_24") (pintype "passive"))
      (node (ref "S1") (pin "41") (pinfunction "GND_41") (pintype "passive"))
      (node (ref "S1") (pin "42") (pinfunction "GND_42") (pintype "passive"))
      (node (ref "S1") (pin "59") (pinfunction "GND_59") (pintype "passive"))
      (node (ref "S1") (pin "60") (pinfunction "GND_60") (pintype "passive"))
      (node (ref "S1") (pin "77") (pinfunction "GND_77") (pintype "passive"))
      (node (ref "S1") (pin "78") (pinfunction "GND_78") (pintype "passive"))
      (node (ref "S1") (pin "95") (pinfunction "GND_95") (pintype "passive"))
      (node (ref "S1") (pin "96") (pinfunction "GND_96") (pintype "passive"))
    )
    (net (code "344") (name "unconnected-(Con7-Pad10)") (class "Default")
      (node (ref "Con7") (pin "10") (pinfunction "10_10") (pintype "passive"))
    )
    (net (code "345") (name "unconnected-(S1A-TCK-Pad99)") (class "Default")
      (node (ref "S1") (pin "99") (pinfunction "TCK_99") (pintype "passive"))
    )
    (net (code "346") (name "unconnected-(S1A-TDI-Pad100)") (class "Default")
      (node (ref "S1") (pin "100") (pinfunction "TDI_100") (pintype "passive"))
    )
    (net (code "347") (name "unconnected-(S1A-TDO-Pad97)") (class "Default")
      (node (ref "S1") (pin "97") (pinfunction "TDO_97") (pintype "passive"))
    )
    (net (code "348") (name "unconnected-(S1A-TMS-Pad98)") (class "Default")
      (node (ref "S1") (pin "98") (pinfunction "TMS_98") (pintype "passive"))
    )
  )
)
